# DC-DC_3V3.net
KiCad netlist of a schematic drawn in Altium Designer
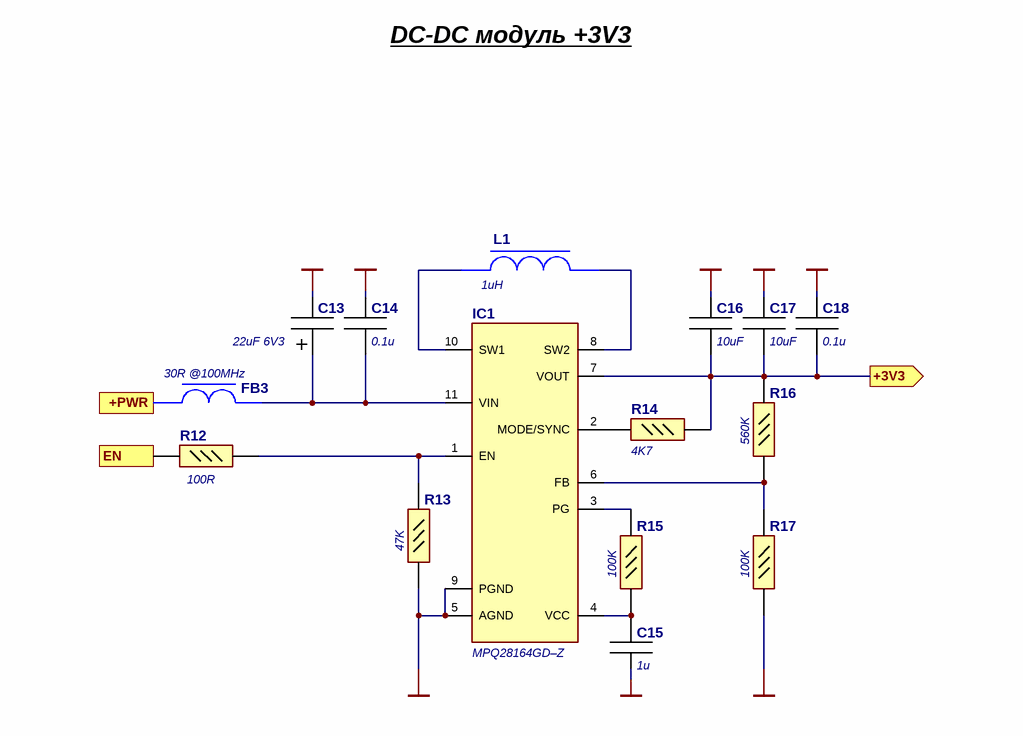
[diagram p0: DC-DC модуль +3V3.SchDoc]

(export (version "E")
  (design (tool "Eeschema 10.0.6"))
  (components
    (comp (ref "C13")
      (value "22uF 6V3")
      (footprint ":CAP1206 C3216-18")
      (description "22uF Molded Tantalum Capacitors 6.3V 1206 (3216 Metric) 300mOhm @ 100kHz")
      (fields (field (name "MANUFACTURER_PART_NUMBER") "TPSA226K006R0300"))
      (libsource (lib "Capacitors 1206") (part "TPSA226K006R0300"))
    )
    (comp (ref "C14")
      (value "0.1u")
      (footprint ":CAP0402 100x50x50")
      (description "±10% 25V Ceramic Capacitor X7R 0402 (1005 Metric)")
      (fields
        (field (name "MANUFACTURER_PART_NUMBER") "GRM155R71E104KE14J")
        (field (name "MOUSER PART NUMBER") "81-GRM155R71E104KE4J")
      )
      (libsource (lib "Capacitors 0402") (part "GRM155R71E104KE14J"))
    )
    (comp (ref "C15")
      (value "1u")
      (footprint ":CAP0603 C1608х08")
      (description "±10% 25V Ceramic Capacitor X7R 0603 (1608 Metric)")
      (fields (field (name "MANUFACTURER_PART_NUMBER") "GCM188R71E105KA64D"))
      (libsource (lib "Capacitors 0603") (part "GCM188R71E105KA64D"))
    )
    (comp (ref "C16")
      (value "10uF")
      (footprint ":CAP0805 C2012X125")
      (description "CAP CER 10uF 16V X5R 0805")
      (fields
        (field (name "MANUFACTURER_PART_NUMBER") "C2012X5R1C106M085AC")
        (field (name "MOUSER PART NUMBER") "810-C2012X5R1C106M-2")
      )
      (libsource (lib "Capacitors 0805") (part "C2012X5R1C106M085AC"))
    )
    (comp (ref "C17")
      (value "10uF")
      (footprint ":CAP0805 C2012X125")
      (description "CAP CER 10uF 16V X5R 0805")
      (fields
        (field (name "MANUFACTURER_PART_NUMBER") "C2012X5R1C106M085AC")
        (field (name "MOUSER PART NUMBER") "810-C2012X5R1C106M-2")
      )
      (libsource (lib "Capacitors 0805") (part "C2012X5R1C106M085AC"))
    )
    (comp (ref "C18")
      (value "0.1u")
      (footprint ":CAP0402 100x50x50")
      (description "±10% 25V Ceramic Capacitor X7R 0402 (1005 Metric)")
      (fields
        (field (name "MANUFACTURER_PART_NUMBER") "GRM155R71E104KE14J")
        (field (name "MOUSER PART NUMBER") "81-GRM155R71E104KE4J")
      )
      (libsource (lib "Capacitors 0402") (part "GRM155R71E104KE14J"))
    )
    (comp (ref "FB3")
      (value "30R @100MHz")
      (footprint ":FER BLM18SP300SN1D")
      (description "30 Ohms @ 100MHz 1 Power Line Ferrite Bead 0603 (1608 Metric) 6A 8mOhm")
      (fields
        (field (name "MANUFACTURER_PART_NUMBER") "BLM18SP300SN1D")
        (field (name "MOUSER PART NUMBER") "81-BLM18SP300SN1D")
      )
      (libsource (lib "Ferrite Bead") (part "BLM18SP300SN1D"))
    )
    (comp (ref "IC1")
      (value "MPQ28164GD–Z")
      (footprint ":QFN11 P300X200X100-11N")
      (description "DC/DC Converter \r\n1.2V to 5.5V Input\r\n1.5V to 5V Output 2A")
      (libsource (lib "DC-DC convertors") (part "MPQ28164GD–Z"))
    )
    (comp (ref "L1")
      (value "1uH")
      (footprint ":IND1210 C3225")
      (fields (field (name "MANUFACTURER_PART_NUMBER") "74479299210"))
      (libsource (lib "Inductance") (part "74479299210"))
    )
    (comp (ref "R12")
      (value "RC0402FR-07")
      (footprint ":RES0402")
      (fields (field (name "MANUFACTURER_PART_NUMBER (PART 2: VALUE)") "100R"))
      (libsource (lib "Resistors 0402") (part "RC0402FR-07"))
    )
    (comp (ref "R13")
      (value "RC0402FR-07")
      (footprint ":RES0402")
      (fields (field (name "MANUFACTURER_PART_NUMBER (PART 2: VALUE)") "47K"))
      (libsource (lib "") (part "RC0402FR-07_1"))
    )
    (comp (ref "R14")
      (value "RC0402FR-07")
      (footprint ":RES0402")
      (fields (field (name "MANUFACTURER_PART_NUMBER (PART 2: VALUE)") "4K7"))
      (libsource (lib "Resistors 0402") (part "RC0402FR-07"))
    )
    (comp (ref "R15")
      (value "RC0402FR-07")
      (footprint ":RES0402")
      (fields (field (name "MANUFACTURER_PART_NUMBER (PART 2: VALUE)") "100K"))
      (libsource (lib "") (part "RC0402FR-07_1"))
    )
    (comp (ref "R16")
      (value "RC0402FR-07")
      (footprint ":RES0402")
      (fields (field (name "MANUFACTURER_PART_NUMBER (PART 2: VALUE)") "560K"))
      (libsource (lib "") (part "RC0402FR-07_1"))
    )
    (comp (ref "R17")
      (value "RC0402FR-07")
      (footprint ":RES0402")
      (fields (field (name "MANUFACTURER_PART_NUMBER (PART 2: VALUE)") "100K"))
      (libsource (lib "") (part "RC0402FR-07_1"))
    )
  )
  (nets
    (net (code "1") (name "/+3V3") (class "Default")
      (node (ref "C16") (pin "1") (pinfunction "1_1") (pintype "passive"))
      (node (ref "C17") (pin "1") (pinfunction "1_1") (pintype "passive"))
      (node (ref "C18") (pin "2") (pinfunction "2_2") (pintype "passive"))
      (node (ref "IC1") (pin "7") (pinfunction "VOUT_7") (pintype "passive"))
      (node (ref "R14") (pin "2") (pinfunction "2_2") (pintype "passive"))
      (node (ref "R16") (pin "2") (pinfunction "2_2") (pintype "passive"))
    )
    (net (code "2") (name "/+PWR") (class "Default")
      (node (ref "FB3") (pin "1") (pinfunction "1_1") (pintype "passive"))
    )
    (net (code "3") (name "/EN") (class "Default")
      (node (ref "R12") (pin "1") (pinfunction "1_1") (pintype "passive"))
    )
    (net (code "4") (name "GND") (class "Default")
      (node (ref "C13") (pin "2") (pinfunction "2_2") (pintype "passive"))
      (node (ref "C14") (pin "1") (pinfunction "1_1") (pintype "passive"))
      (node (ref "C15") (pin "1") (pinfunction "1_1") (pintype "passive"))
      (node (ref "C16") (pin "2") (pinfunction "2_2") (pintype "passive"))
      (node (ref "C17") (pin "2") (pinfunction "2_2") (pintype "passive"))
      (node (ref "C18") (pin "1") (pinfunction "1_1") (pintype "passive"))
      (node (ref "IC1") (pin "5") (pinfunction "AGND_5") (pintype "passive"))
      (node (ref "IC1") (pin "9") (pinfunction "PGND_9") (pintype "passive"))
      (node (ref "R13") (pin "1") (pinfunction "1_1") (pintype "passive"))
      (node (ref "R17") (pin "1") (pinfunction "1_1") (pintype "passive"))
    )
    (net (code "5") (name "Net-(C13-+)") (class "Default")
      (node (ref "C13") (pin "1") (pinfunction "+_1") (pintype "passive"))
      (node (ref "C14") (pin "2") (pinfunction "2_2") (pintype "passive"))
      (node (ref "FB3") (pin "2") (pinfunction "2_2") (pintype "passive"))
      (node (ref "IC1") (pin "11") (pinfunction "VIN_11") (pintype "passive"))
    )
    (net (code "6") (name "Net-(IC1-EN)") (class "Default")
      (node (ref "IC1") (pin "1") (pinfunction "EN_1") (pintype "passive"))
      (node (ref "R12") (pin "2") (pinfunction "2_2") (pintype "passive"))
      (node (ref "R13") (pin "2") (pinfunction "2_2") (pintype "passive"))
    )
    (net (code "7") (name "Net-(IC1-FB)") (class "Default")
      (node (ref "IC1") (pin "6") (pinfunction "FB_6") (pintype "passive"))
      (node (ref "R16") (pin "1") (pinfunction "1_1") (pintype "passive"))
      (node (ref "R17") (pin "2") (pinfunction "2_2") (pintype "passive"))
    )
    (net (code "8") (name "Net-(IC1-MODE{slash}SYNC)") (class "Default")
      (node (ref "IC1") (pin "2") (pinfunction "MODE/SYNC_2") (pintype "passive"))
      (node (ref "R14") (pin "1") (pinfunction "1_1") (pintype "passive"))
    )
    (net (code "9") (name "Net-(IC1-PG)") (class "Default")
      (node (ref "IC1") (pin "3") (pinfunction "PG_3") (pintype "passive"))
      (node (ref "R15") (pin "2") (pinfunction "2_2") (pintype "passive"))
    )
    (net (code "10") (name "Net-(IC1-SW1)") (class "Default")
      (node (ref "IC1") (pin "10") (pinfunction "SW1_10") (pintype "passive"))
      (node (ref "L1") (pin "1") (pinfunction "1_1") (pintype "passive"))
    )
    (net (code "11") (name "Net-(IC1-SW2)") (class "Default")
      (node (ref "IC1") (pin "8") (pinfunction "SW2_8") (pintype "passive"))
      (node (ref "L1") (pin "2") (pinfunction "2_2") (pintype "passive"))
    )
    (net (code "12") (name "Net-(IC1-VCC)") (class "Default")
      (node (ref "C15") (pin "2") (pinfunction "2_2") (pintype "passive"))
      (node (ref "IC1") (pin "4") (pinfunction "VCC_4") (pintype "passive"))
      (node (ref "R15") (pin "1") (pinfunction "1_1") (pintype "passive"))
    )
  )
)
